# design.net
KiCad netlist of a schematic drawn in EasyEDA Pro
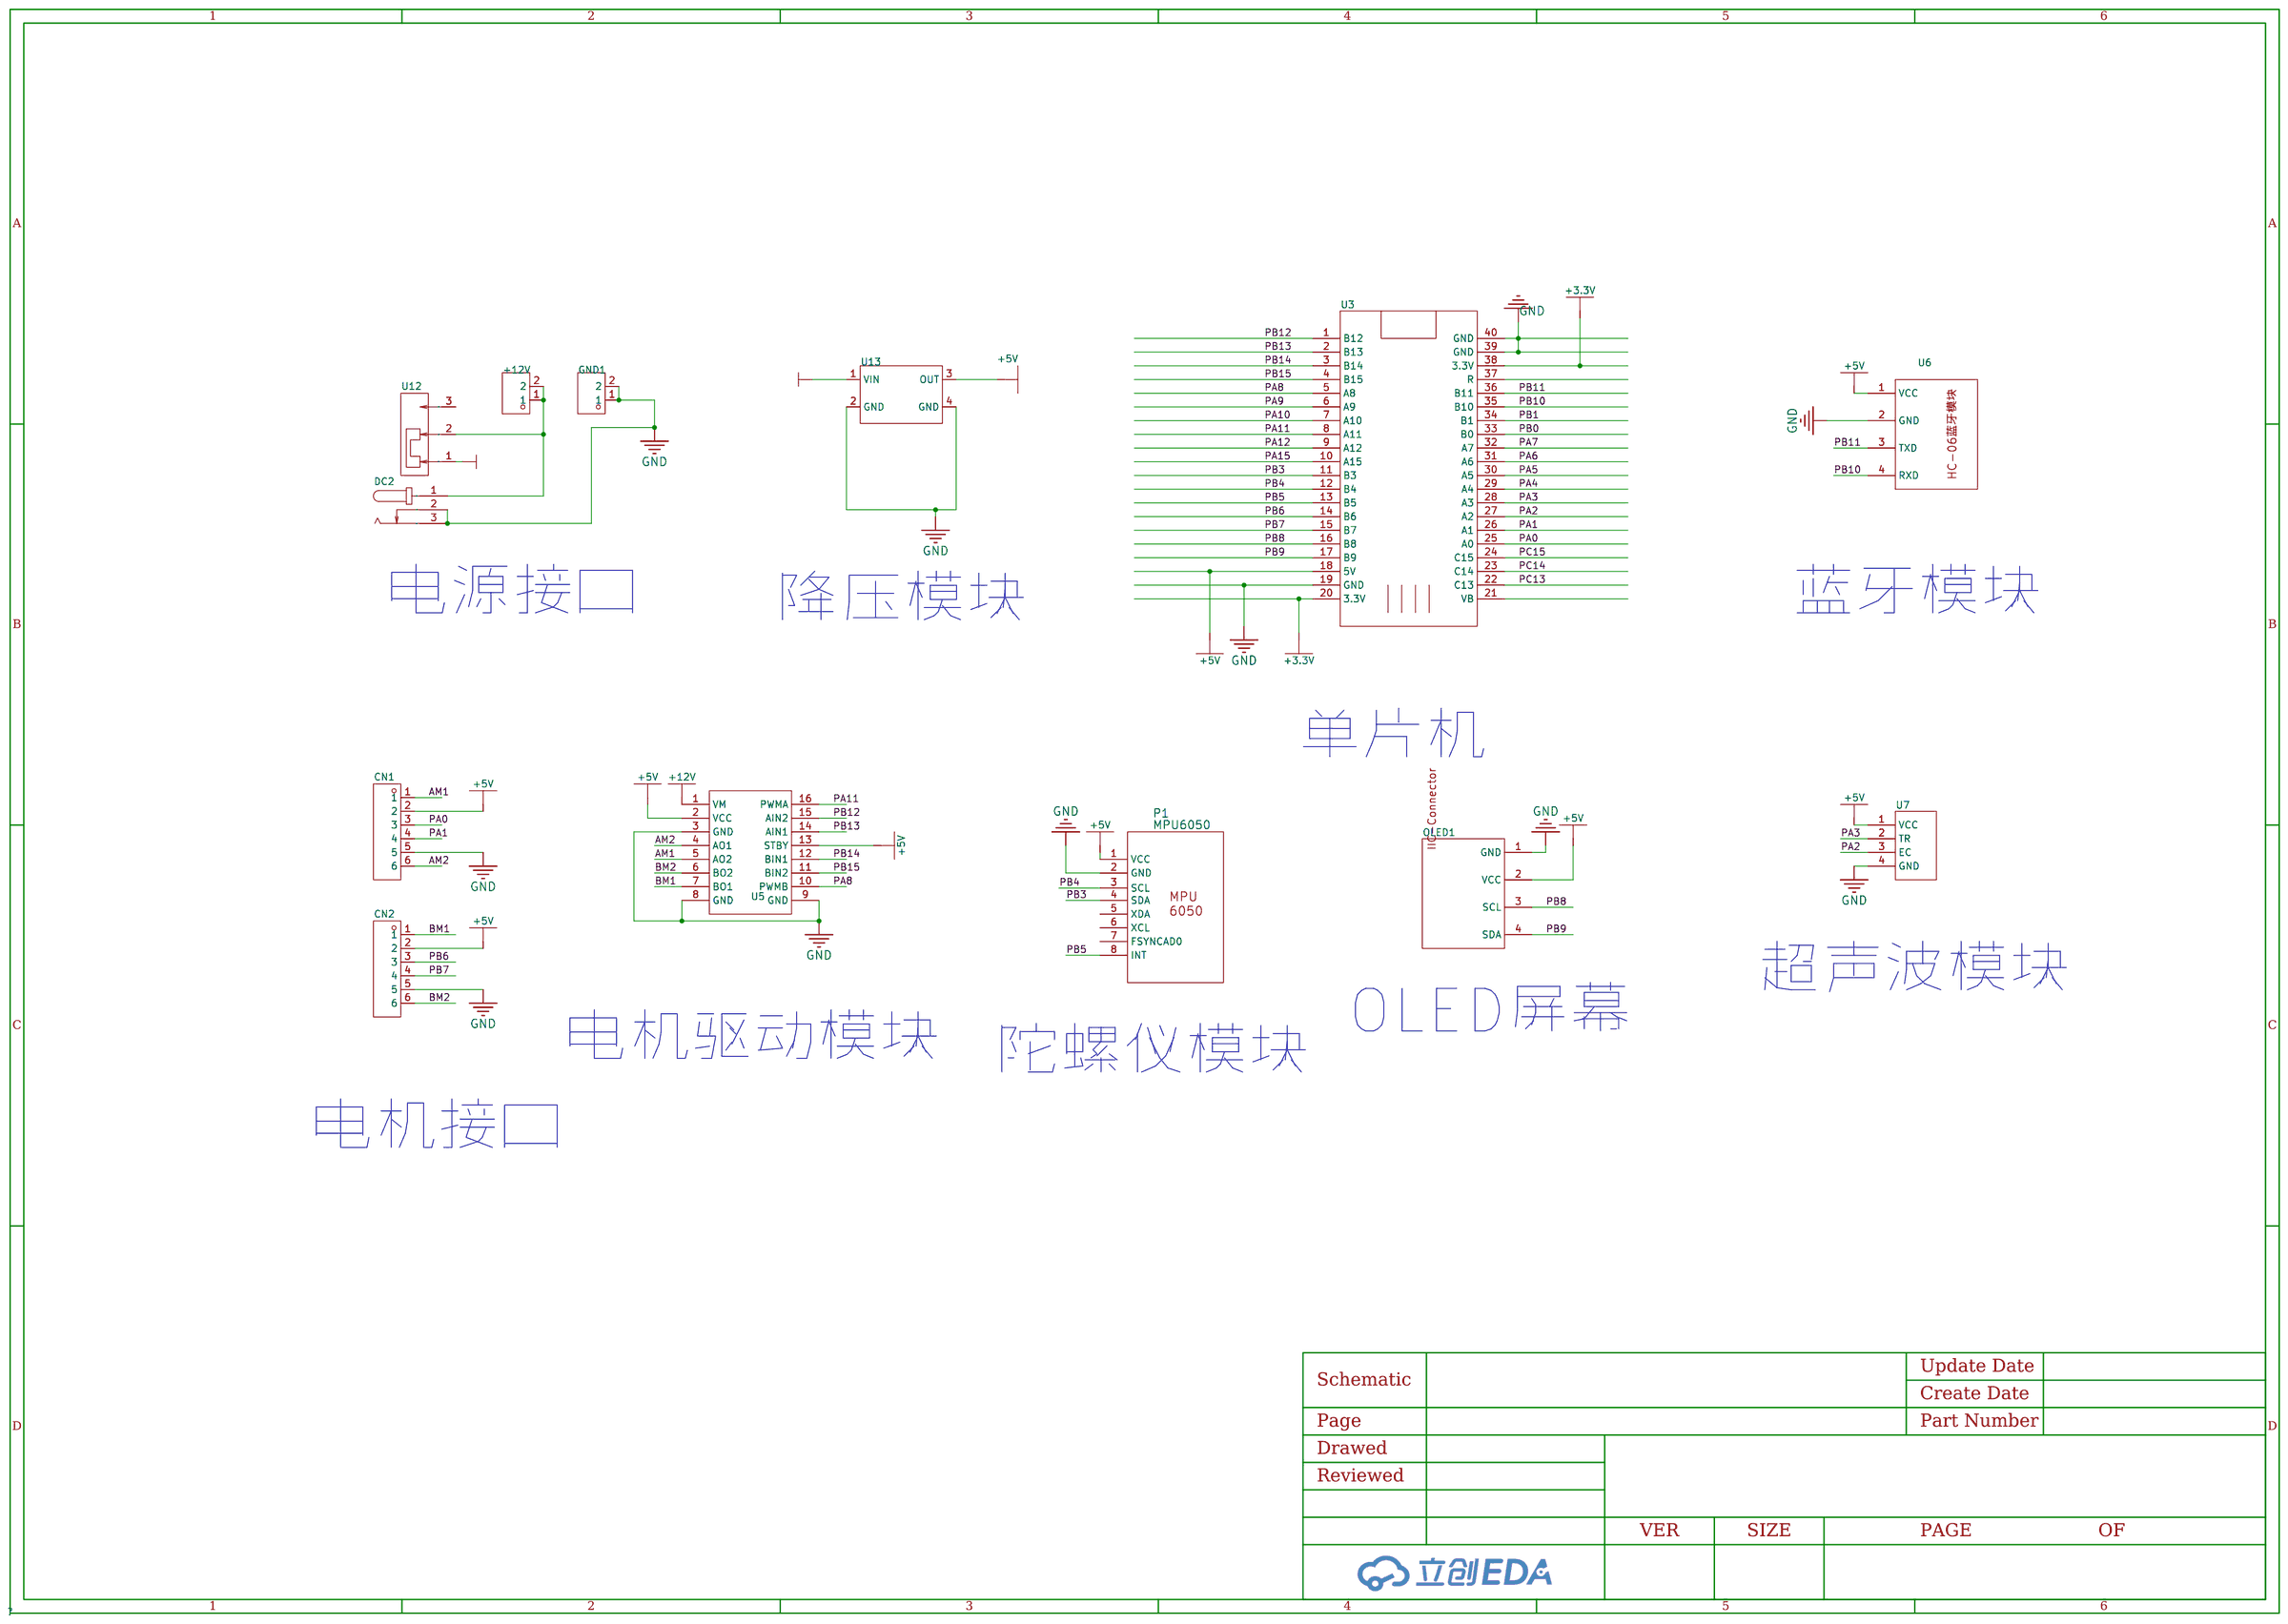
[diagram p0: schematic sheet]

(export (version "E")
  (design (tool "Eeschema 10.0.6"))
  (components
    (comp (ref "+12V")
      (value "~")
      (description "2.54 1*2P 直排针 0.8u镀金 PBT RoHS,针长3*6mm")
      (fields
        (field (name "Manufacturer Part") "Z-211-0211-0021-001")
        (field (name "Manufacturer") "Nextron(台湾正凌)")
      )
      (libsource (lib "easyedapro") (part "Z-211-0211-0021-001"))
    )
    (comp (ref "CN1")
      (value "PH2.0-6P")
      (fields (field (name "Manufacturer Part") "PH2.0-4P") (field (name "Manufacturer") "CAX(创都)"))
      (libsource (lib "easyedapro") (part "PH2.0-6P"))
    )
    (comp (ref "CN2")
      (value "PH2.0-6P")
      (fields (field (name "Manufacturer Part") "PH2.0-4P") (field (name "Manufacturer") "CAX(创都)"))
      (libsource (lib "easyedapro") (part "PH2.0-6P"))
    )
    (comp (ref "DC2")
      (value "~")
      (description "连接器类型:DC电源插座;安装方式:弯插;触点内径:-;触点外径:6.4mm;额定电流:1A;额定电压:30V;工作温度范围:-25~+70;")
      (fields
        (field (name "Manufacturer Part") "KH-DC-005-2.5")
        (field (name "Manufacturer") "kinghelm(金航标)")
      )
      (libsource (lib "easyedapro") (part "KH-DC-005-2.5"))
    )
    (comp (ref "GND1")
      (value "~")
      (description "2.54 1*2P 直排针 0.8u镀金 PBT RoHS,针长3*6mm")
      (fields
        (field (name "Manufacturer Part") "Z-211-0211-0021-001")
        (field (name "Manufacturer") "Nextron(台湾正凌)")
      )
      (libsource (lib "easyedapro") (part "Z-211-0211-0021-001"))
    )
    (comp (ref "OLED1")
      (value "~")
      (fields (field (name "Manufacturer Part") "0.96OLED_4P_MODULE_JX"))
      (libsource (lib "easyedapro") (part "0.96OLED_4P_MODULE_JX"))
    )
    (comp (ref "P1") (value "MPU6050") (libsource (lib "easyedapro") (part "MPU6050")))
    (comp (ref "U3") (value "~") (libsource (lib "easyedapro") (part "STM32F103C8T6核心板")))
    (comp (ref "U5") (value "~") (libsource (lib "easyedapro") (part "TB6612FNG模块")))
    (comp (ref "U6") (value "蓝牙模块HC-06") (libsource (lib "easyedapro") (part "蓝牙模块HC-06")))
    (comp (ref "U7") (value "~") (libsource (lib "easyedapro") (part "HC-SR04")))
    (comp (ref "U12")
      (value "SS-12D10-G5")
      (footprint "easyedapro:SW-TH_SS-12D10-G050")
      (description "电路结构:单刀双掷;安装方式:直插;开关颜色:黑色;滑钮形状:矩形柱状;引脚样式:PC引脚;开关长度:12.7mm;开关宽度:6.7mm;开关高度:11.3mm;")
      (fields (field (name "Manufacturer") "DEALON(德艺隆)"))
      (libsource (lib "easyedapro") (part "SS-12D10-G5"))
    )
    (comp (ref "U13")
      (value "~")
      (footprint "easyedapro:MP1584模块")
      (libsource (lib "easyedapro") (part "MP1584模块"))
    )
  )
  (nets
    (net (code "1") (name "+3.3V") (class "Default")
      (node (ref "U3") (pin "20") (pinfunction "3.3V_20") (pintype "unspecified"))
      (node (ref "U3") (pin "38") (pinfunction "3.3V_38") (pintype "unspecified"))
    )
    (net (code "2") (name "+5V") (class "Default")
      (node (ref "CN1") (pin "2") (pinfunction "2_2") (pintype "input"))
      (node (ref "CN2") (pin "2") (pinfunction "2_2") (pintype "input"))
      (node (ref "OLED1") (pin "2") (pinfunction "VCC_2") (pintype "input"))
      (node (ref "P1") (pin "1") (pinfunction "VCC_1") (pintype "input"))
      (node (ref "U13") (pin "3") (pinfunction "OUT_3") (pintype "unspecified"))
      (node (ref "U3") (pin "18") (pinfunction "5V_18") (pintype "unspecified"))
      (node (ref "U5") (pin "13") (pinfunction "STBY_13") (pintype "input"))
      (node (ref "U5") (pin "2") (pinfunction "VCC_2") (pintype "input"))
      (node (ref "U6") (pin "1") (pinfunction "VCC_1") (pintype "unspecified"))
      (node (ref "U7") (pin "1") (pinfunction "VCC_1") (pintype "input"))
    )
    (net (code "3") (name "+12V") (class "Default")
      (node (ref "U12") (pin "1") (pinfunction "1_1") (pintype "input"))
      (node (ref "U13") (pin "1") (pinfunction "VIN_1") (pintype "unspecified"))
      (node (ref "U5") (pin "1") (pinfunction "VM_1") (pintype "input"))
    )
    (net (code "4") (name "/AM1") (class "Default")
      (node (ref "CN1") (pin "1") (pinfunction "1_1") (pintype "input"))
      (node (ref "U5") (pin "5") (pinfunction "AO2_5") (pintype "input"))
    )
    (net (code "5") (name "/AM2") (class "Default")
      (node (ref "CN1") (pin "6") (pinfunction "6_6") (pintype "input"))
      (node (ref "U5") (pin "4") (pinfunction "AO1_4") (pintype "input"))
    )
    (net (code "6") (name "/BM1") (class "Default")
      (node (ref "CN2") (pin "1") (pinfunction "1_1") (pintype "input"))
      (node (ref "U5") (pin "7") (pinfunction "BO1_7") (pintype "input"))
    )
    (net (code "7") (name "/BM2") (class "Default")
      (node (ref "CN2") (pin "6") (pinfunction "6_6") (pintype "input"))
      (node (ref "U5") (pin "6") (pinfunction "BO2_6") (pintype "input"))
    )
    (net (code "8") (name "/PA0") (class "Default")
      (node (ref "CN1") (pin "3") (pinfunction "3_3") (pintype "input"))
      (node (ref "U3") (pin "25") (pinfunction "A0_25") (pintype "unspecified"))
    )
    (net (code "9") (name "/PA1") (class "Default")
      (node (ref "CN1") (pin "4") (pinfunction "4_4") (pintype "input"))
      (node (ref "U3") (pin "26") (pinfunction "A1_26") (pintype "unspecified"))
    )
    (net (code "10") (name "/PA2") (class "Default")
      (node (ref "U3") (pin "27") (pinfunction "A2_27") (pintype "unspecified"))
      (node (ref "U7") (pin "3") (pinfunction "EC_3") (pintype "input"))
    )
    (net (code "11") (name "/PA3") (class "Default")
      (node (ref "U3") (pin "28") (pinfunction "A3_28") (pintype "unspecified"))
      (node (ref "U7") (pin "2") (pinfunction "TR_2") (pintype "input"))
    )
    (net (code "12") (name "/PA4") (class "Default")
      (node (ref "U3") (pin "29") (pinfunction "A4_29") (pintype "unspecified"))
    )
    (net (code "13") (name "/PA5") (class "Default")
      (node (ref "U3") (pin "30") (pinfunction "A5_30") (pintype "unspecified"))
    )
    (net (code "14") (name "/PA6") (class "Default")
      (node (ref "U3") (pin "31") (pinfunction "A6_31") (pintype "unspecified"))
    )
    (net (code "15") (name "/PA7") (class "Default")
      (node (ref "U3") (pin "32") (pinfunction "A7_32") (pintype "unspecified"))
    )
    (net (code "16") (name "/PA8") (class "Default")
      (node (ref "U3") (pin "5") (pinfunction "A8_5") (pintype "unspecified"))
      (node (ref "U5") (pin "10") (pinfunction "PWMB_10") (pintype "input"))
    )
    (net (code "17") (name "/PA9") (class "Default")
      (node (ref "U3") (pin "6") (pinfunction "A9_6") (pintype "unspecified"))
    )
    (net (code "18") (name "/PA10") (class "Default")
      (node (ref "U3") (pin "7") (pinfunction "A10_7") (pintype "unspecified"))
    )
    (net (code "19") (name "/PA11") (class "Default")
      (node (ref "U3") (pin "8") (pinfunction "A11_8") (pintype "unspecified"))
      (node (ref "U5") (pin "16") (pinfunction "PWMA_16") (pintype "input"))
    )
    (net (code "20") (name "/PA12") (class "Default")
      (node (ref "U3") (pin "9") (pinfunction "A12_9") (pintype "unspecified"))
    )
    (net (code "21") (name "/PA15") (class "Default")
      (node (ref "U3") (pin "10") (pinfunction "A15_10") (pintype "unspecified"))
    )
    (net (code "22") (name "/PB0") (class "Default")
      (node (ref "U3") (pin "33") (pinfunction "B0_33") (pintype "unspecified"))
    )
    (net (code "23") (name "/PB1") (class "Default")
      (node (ref "U3") (pin "34") (pinfunction "B1_34") (pintype "unspecified"))
    )
    (net (code "24") (name "/PB3") (class "Default")
      (node (ref "P1") (pin "4") (pinfunction "SDA_4") (pintype "input"))
      (node (ref "U3") (pin "11") (pinfunction "B3_11") (pintype "unspecified"))
    )
    (net (code "25") (name "/PB4") (class "Default")
      (node (ref "P1") (pin "3") (pinfunction "SCL_3") (pintype "input"))
      (node (ref "U3") (pin "12") (pinfunction "B4_12") (pintype "unspecified"))
    )
    (net (code "26") (name "/PB5") (class "Default")
      (node (ref "P1") (pin "8") (pinfunction "INT_8") (pintype "input"))
      (node (ref "U3") (pin "13") (pinfunction "B5_13") (pintype "unspecified"))
    )
    (net (code "27") (name "/PB6") (class "Default")
      (node (ref "CN2") (pin "3") (pinfunction "3_3") (pintype "input"))
      (node (ref "U3") (pin "14") (pinfunction "B6_14") (pintype "unspecified"))
    )
    (net (code "28") (name "/PB7") (class "Default")
      (node (ref "CN2") (pin "4") (pinfunction "4_4") (pintype "input"))
      (node (ref "U3") (pin "15") (pinfunction "B7_15") (pintype "unspecified"))
    )
    (net (code "29") (name "/PB8") (class "Default")
      (node (ref "OLED1") (pin "3") (pinfunction "SCL_3") (pintype "input"))
      (node (ref "U3") (pin "16") (pinfunction "B8_16") (pintype "unspecified"))
    )
    (net (code "30") (name "/PB9") (class "Default")
      (node (ref "OLED1") (pin "4") (pinfunction "SDA_4") (pintype "input"))
      (node (ref "U3") (pin "17") (pinfunction "B9_17") (pintype "unspecified"))
    )
    (net (code "31") (name "/PB10") (class "Default")
      (node (ref "U3") (pin "35") (pinfunction "B10_35") (pintype "unspecified"))
      (node (ref "U6") (pin "4") (pinfunction "RXD_4") (pintype "unspecified"))
    )
    (net (code "32") (name "/PB11") (class "Default")
      (node (ref "U3") (pin "36") (pinfunction "B11_36") (pintype "unspecified"))
      (node (ref "U6") (pin "3") (pinfunction "TXD_3") (pintype "unspecified"))
    )
    (net (code "33") (name "/PB12") (class "Default")
      (node (ref "U3") (pin "1") (pinfunction "B12_1") (pintype "unspecified"))
      (node (ref "U5") (pin "15") (pinfunction "AIN2_15") (pintype "input"))
    )
    (net (code "34") (name "/PB13") (class "Default")
      (node (ref "U3") (pin "2") (pinfunction "B13_2") (pintype "unspecified"))
      (node (ref "U5") (pin "14") (pinfunction "AIN1_14") (pintype "input"))
    )
    (net (code "35") (name "/PB14") (class "Default")
      (node (ref "U3") (pin "3") (pinfunction "B14_3") (pintype "unspecified"))
      (node (ref "U5") (pin "12") (pinfunction "BIN1_12") (pintype "input"))
    )
    (net (code "36") (name "/PB15") (class "Default")
      (node (ref "U3") (pin "4") (pinfunction "B15_4") (pintype "unspecified"))
      (node (ref "U5") (pin "11") (pinfunction "BIN2_11") (pintype "input"))
    )
    (net (code "37") (name "/PC13") (class "Default")
      (node (ref "U3") (pin "22") (pinfunction "C13_22") (pintype "unspecified"))
    )
    (net (code "38") (name "/PC14") (class "Default")
      (node (ref "U3") (pin "23") (pinfunction "C14_23") (pintype "unspecified"))
    )
    (net (code "39") (name "/PC15") (class "Default")
      (node (ref "U3") (pin "24") (pinfunction "C15_24") (pintype "unspecified"))
    )
    (net (code "40") (name "GND") (class "Default")
      (node (ref "CN1") (pin "5") (pinfunction "5_5") (pintype "input"))
      (node (ref "CN2") (pin "5") (pinfunction "5_5") (pintype "input"))
      (node (ref "DC2") (pin "2") (pinfunction "2_2") (pintype "input"))
      (node (ref "DC2") (pin "3") (pinfunction "3_3") (pintype "input"))
      (node (ref "GND1") (pin "1") (pinfunction "1_1") (pintype "input"))
      (node (ref "GND1") (pin "2") (pinfunction "2_2") (pintype "input"))
      (node (ref "OLED1") (pin "1") (pinfunction "GND_1") (pintype "input"))
      (node (ref "P1") (pin "2") (pinfunction "GND_2") (pintype "input"))
      (node (ref "U13") (pin "2") (pinfunction "GND_2") (pintype "unspecified"))
      (node (ref "U13") (pin "4") (pinfunction "GND_4") (pintype "unspecified"))
      (node (ref "U3") (pin "19") (pinfunction "GND_19") (pintype "unspecified"))
      (node (ref "U3") (pin "39") (pinfunction "GND_39") (pintype "unspecified"))
      (node (ref "U3") (pin "40") (pinfunction "GND_40") (pintype "unspecified"))
      (node (ref "U5") (pin "3") (pinfunction "GND_3") (pintype "input"))
      (node (ref "U5") (pin "8") (pinfunction "GND_8") (pintype "input"))
      (node (ref "U5") (pin "9") (pinfunction "GND_9") (pintype "input"))
      (node (ref "U6") (pin "2") (pinfunction "GND_2") (pintype "unspecified"))
      (node (ref "U7") (pin "4") (pinfunction "GND_4") (pintype "input"))
    )
    (net (code "41") (name "Net-(+12V-Pad1)") (class "Default")
      (node (ref "+12V") (pin "1") (pinfunction "1_1") (pintype "input"))
      (node (ref "+12V") (pin "2") (pinfunction "2_2") (pintype "input"))
      (node (ref "DC2") (pin "1") (pinfunction "1_1") (pintype "input"))
      (node (ref "U12") (pin "2") (pinfunction "2_2") (pintype "input"))
    )
    (net (code "42") (name "unconnected-(P1-FSYNCAD0-Pad7)") (class "Default")
      (node (ref "P1") (pin "7") (pinfunction "FSYNCAD0_7") (pintype "input"))
    )
    (net (code "43") (name "unconnected-(P1-XCL-Pad6)") (class "Default")
      (node (ref "P1") (pin "6") (pinfunction "XCL_6") (pintype "input"))
    )
    (net (code "44") (name "unconnected-(P1-XDA-Pad5)") (class "Default")
      (node (ref "P1") (pin "5") (pinfunction "XDA_5") (pintype "input"))
    )
    (net (code "45") (name "unconnected-(U3-R-Pad37)") (class "Default")
      (node (ref "U3") (pin "37") (pinfunction "R_37") (pintype "unspecified"))
    )
    (net (code "46") (name "unconnected-(U3-VB-Pad21)") (class "Default")
      (node (ref "U3") (pin "21") (pinfunction "VB_21") (pintype "unspecified"))
    )
    (net (code "47") (name "unconnected-(U12-Pad3)") (class "Default")
      (node (ref "U12") (pin "3") (pinfunction "3_3") (pintype "input"))
    )
  )
)
